# PART-03-_R150-199.net
KiCad netlist of a schematic drawn in Altium Designer
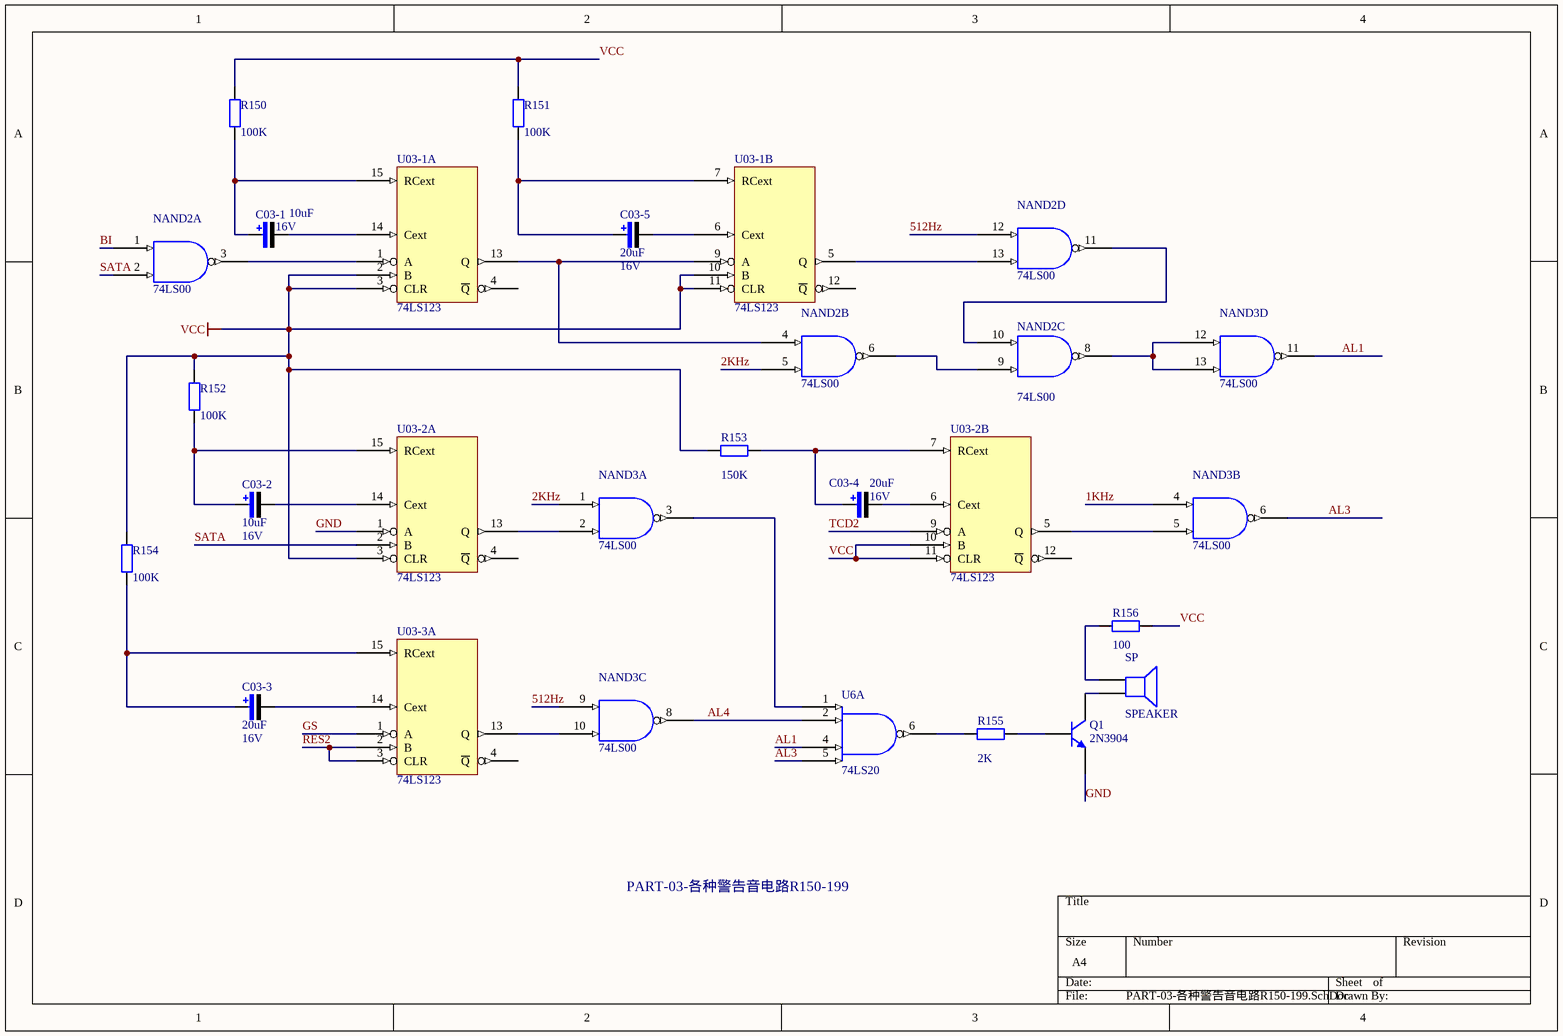
[diagram p0: PART-03-各种警告音电路R150-199.SchDoc]

(export (version "E")
  (design (tool "Eeschema 10.0.6"))
  (components
    (comp (ref "C03-1")
      (value "10uF")
      (footprint "C-RB-18")
      (description "极性电解电容")
      (fields
        (field (name "VOL") "16V")
        (field (name "Comment") "Cap Pol")
        (field (name "PUBLISHER") "Altium Limited")
      )
      (libsource (lib "Fszhang") (part "Cap Pol"))
    )
    (comp (ref "C03-2")
      (value "10uF")
      (footprint "C-RB-18")
      (description "极性电解电容")
      (fields
        (field (name "VOL") "16V")
        (field (name "Comment") "Cap Pol")
        (field (name "PUBLISHER") "Altium Limited")
      )
      (libsource (lib "Fszhang") (part "Cap Pol"))
    )
    (comp (ref "C03-3")
      (value "20uF")
      (footprint "C-RB-18")
      (description "极性电解电容")
      (fields
        (field (name "VOL") "16V")
        (field (name "Comment") "Cap Pol")
        (field (name "PUBLISHER") "Altium Limited")
      )
      (libsource (lib "Fszhang") (part "Cap Pol"))
    )
    (comp (ref "C03-4")
      (value "20uF")
      (footprint "C-RB-18")
      (description "极性电解电容")
      (fields
        (field (name "VOL") "16V")
        (field (name "Comment") "Cap Pol")
        (field (name "PUBLISHER") "Altium Limited")
      )
      (libsource (lib "Fszhang") (part "Cap Pol"))
    )
    (comp (ref "C03-5")
      (value "20uF")
      (footprint "C-RB-18")
      (description "极性电解电容")
      (fields
        (field (name "VOL") "16V")
        (field (name "Comment") "Cap Pol")
        (field (name "PUBLISHER") "Altium Limited")
      )
      (libsource (lib "Fszhang") (part "Cap Pol"))
    )
    (comp (ref "NAND2")
      (value "74LS00")
      (footprint "DIP-14")
      (libsource (lib "Protel DOS Schematic TTL") (part "74LS00"))
    )
    (comp (ref "NAND3")
      (value "74LS00")
      (footprint "DIP-14")
      (libsource (lib "Protel DOS Schematic TTL") (part "74LS00"))
    )
    (comp (ref "Q1")
      (value "2N3904")
      (footprint "TO-92A")
      (description "NPN General Purpose Amplifier")
      (fields (field (name "PUBLISHER") "Altium Limited"))
      (libsource (lib "Miscellaneous Devices") (part "2N3904"))
    )
    (comp (ref "R150")
      (value "100K")
      (footprint "AXIAL-0.4")
      (description "Resistor")
      (fields (field (name "Comment") "Res2") (field (name "PUBLISHER") "Altium Limited"))
      (libsource (lib "Miscellaneous Devices") (part "Res2"))
    )
    (comp (ref "R151")
      (value "100K")
      (footprint "AXIAL-0.4")
      (description "Resistor")
      (fields (field (name "Comment") "Res2") (field (name "PUBLISHER") "Altium Limited"))
      (libsource (lib "Miscellaneous Devices") (part "Res2"))
    )
    (comp (ref "R152")
      (value "100K")
      (footprint "AXIAL-0.4")
      (description "Resistor")
      (fields (field (name "Comment") "Res2") (field (name "PUBLISHER") "Altium Limited"))
      (libsource (lib "Miscellaneous Devices") (part "Res2"))
    )
    (comp (ref "R153")
      (value "150K")
      (footprint "AXIAL-0.4")
      (description "Resistor")
      (fields (field (name "Comment") "Res2") (field (name "PUBLISHER") "Altium Limited"))
      (libsource (lib "") (part "Res2_1"))
    )
    (comp (ref "R154")
      (value "100K")
      (footprint "AXIAL-0.4")
      (description "Resistor")
      (fields (field (name "Comment") "Res2") (field (name "PUBLISHER") "Altium Limited"))
      (libsource (lib "Miscellaneous Devices") (part "Res2"))
    )
    (comp (ref "R155")
      (value "2K")
      (footprint "AXIAL-0.4")
      (description "Resistor")
      (fields (field (name "Comment") "Res2") (field (name "PUBLISHER") "Altium Limited"))
      (libsource (lib "") (part "Res2_1"))
    )
    (comp (ref "R156")
      (value "100")
      (footprint "AXIAL-0.4")
      (description "Resistor")
      (fields (field (name "Comment") "Res2") (field (name "PUBLISHER") "Altium Limited"))
      (libsource (lib "") (part "Res2_1"))
    )
    (comp (ref "SP") (value "SPEAKER") (libsource (lib "Miscellaneous Devices") (part "SPEAKER")))
    (comp (ref "U03-1")
      (value "74LS123")
      (footprint "DIP-16")
      (libsource (lib "Protel DOS Schematic TTL") (part "74LS123"))
    )
    (comp (ref "U03-2")
      (value "74LS123")
      (footprint "DIP-16")
      (libsource (lib "Protel DOS Schematic TTL") (part "74LS123"))
    )
    (comp (ref "U03-3")
      (value "74LS123")
      (footprint "DIP-16")
      (libsource (lib "Protel DOS Schematic TTL") (part "74LS123"))
    )
    (comp (ref "U6") (value "74LS20") (footprint "DIP-14") (libsource (lib "Schematic TTL") (part "74LS20")))
  )
  (nets
    (net (code "1") (name "/1KHz") (class "Default") (node (ref "NAND3") (pin "4") (pintype "input")))
    (net (code "2") (name "/2KHz") (class "Default")
      (node (ref "NAND2") (pin "5") (pintype "input"))
      (node (ref "NAND3") (pin "1") (pintype "input"))
    )
    (net (code "3") (name "/512Hz") (class "Default")
      (node (ref "NAND2") (pin "12") (pintype "input"))
      (node (ref "NAND3") (pin "9") (pintype "input"))
    )
    (net (code "4") (name "/AL1") (class "Default")
      (node (ref "NAND3") (pin "11") (pintype "output"))
      (node (ref "U6") (pin "4") (pintype "input"))
    )
    (net (code "5") (name "/AL3") (class "Default")
      (node (ref "NAND3") (pin "6") (pintype "output"))
      (node (ref "U6") (pin "5") (pintype "input"))
    )
    (net (code "6") (name "/AL4") (class "Default")
      (node (ref "NAND3") (pin "8") (pintype "output"))
      (node (ref "U6") (pin "2") (pintype "input"))
    )
    (net (code "7") (name "/BI") (class "Default") (node (ref "NAND2") (pin "1") (pintype "input")))
    (net (code "8") (name "/GS") (class "Default")
      (node (ref "U03-3") (pin "1") (pinfunction "A_1") (pintype "input"))
    )
    (net (code "9") (name "/RES2") (class "Default")
      (node (ref "U03-3") (pin "2") (pinfunction "B_2") (pintype "input"))
      (node (ref "U03-3") (pin "3") (pinfunction "CLR_3") (pintype "input"))
    )
    (net (code "10") (name "/SATA") (class "Default")
      (node (ref "NAND2") (pin "2") (pintype "input"))
      (node (ref "U03-2") (pin "2") (pinfunction "B_2") (pintype "input"))
    )
    (net (code "11") (name "/TCD2") (class "Default")
      (node (ref "U03-2") (pin "9") (pinfunction "A_9") (pintype "input"))
    )
    (net (code "12") (name "GND") (class "Default")
      (node (ref "NAND2") (pin "7") (pinfunction "GND_7") (pintype "power_in"))
      (node (ref "NAND3") (pin "7") (pinfunction "GND_7") (pintype "power_in"))
      (node (ref "Q1") (pin "1") (pinfunction "E_1") (pintype "passive"))
      (node (ref "U03-1") (pin "8") (pinfunction "GND_8") (pintype "power_in"))
      (node (ref "U03-2") (pin "1") (pinfunction "A_1") (pintype "input"))
      (node (ref "U03-2") (pin "8") (pinfunction "GND_8") (pintype "power_in"))
      (node (ref "U03-3") (pin "8") (pinfunction "GND_8") (pintype "power_in"))
      (node (ref "U6") (pin "7") (pinfunction "GND_7") (pintype "power_in"))
    )
    (net (code "13") (name "Net-(NAND2-Pad6)") (class "Default")
      (node (ref "NAND2") (pin "6") (pintype "output"))
      (node (ref "NAND2") (pin "9") (pintype "input"))
    )
    (net (code "14") (name "Net-(NAND2-Pad8)") (class "Default")
      (node (ref "NAND2") (pin "8") (pintype "output"))
      (node (ref "NAND3") (pin "12") (pintype "input"))
      (node (ref "NAND3") (pin "13") (pintype "input"))
    )
    (net (code "15") (name "Net-(NAND2-Pad10)") (class "Default")
      (node (ref "NAND2") (pin "10") (pintype "input"))
      (node (ref "NAND2") (pin "11") (pintype "output"))
    )
    (net (code "16") (name "Net-(NAND3-Pad3)") (class "Default")
      (node (ref "NAND3") (pin "3") (pintype "output"))
      (node (ref "U6") (pin "1") (pintype "input"))
    )
    (net (code "17") (name "Net-(Q1-B)") (class "Default")
      (node (ref "Q1") (pin "2") (pinfunction "B_2") (pintype "passive"))
      (node (ref "R155") (pin "2") (pinfunction "2_2") (pintype "passive"))
    )
    (net (code "18") (name "Net-(Q1-C)") (class "Default")
      (node (ref "Q1") (pin "3") (pinfunction "C_3") (pintype "passive"))
      (node (ref "SP") (pin "2") (pinfunction "2_2") (pintype "passive"))
    )
    (net (code "19") (name "Net-(R155-Pad1)") (class "Default")
      (node (ref "R155") (pin "1") (pinfunction "1_1") (pintype "passive"))
      (node (ref "U6") (pin "6") (pintype "output"))
    )
    (net (code "20") (name "Net-(R156-Pad1)") (class "Default")
      (node (ref "R156") (pin "1") (pinfunction "1_1") (pintype "passive"))
      (node (ref "SP") (pin "1") (pinfunction "1_1") (pintype "passive"))
    )
    (net (code "21") (name "Net-(U03-1A-A)") (class "Default")
      (node (ref "NAND2") (pin "3") (pintype "output"))
      (node (ref "U03-1") (pin "1") (pinfunction "A_1") (pintype "input"))
    )
    (net (code "22") (name "Net-(U03-1A-Cext)") (class "Default")
      (node (ref "C03-1") (pin "2") (pinfunction "2_2") (pintype "passive"))
      (node (ref "U03-1") (pin "14") (pinfunction "Cext_14") (pintype "input"))
    )
    (net (code "23") (name "Net-(U03-1A-Q)") (class "Default")
      (node (ref "NAND2") (pin "4") (pintype "input"))
      (node (ref "U03-1") (pin "13") (pinfunction "Q_13") (pintype "output"))
      (node (ref "U03-1") (pin "9") (pinfunction "A_9") (pintype "input"))
    )
    (net (code "24") (name "Net-(U03-1A-RCext)") (class "Default")
      (node (ref "C03-1") (pin "1") (pinfunction "1_1") (pintype "passive"))
      (node (ref "R150") (pin "1") (pinfunction "1_1") (pintype "passive"))
      (node (ref "U03-1") (pin "15") (pinfunction "RCext_15") (pintype "input"))
    )
    (net (code "25") (name "Net-(U03-1B-Cext)") (class "Default")
      (node (ref "C03-5") (pin "2") (pinfunction "2_2") (pintype "passive"))
      (node (ref "U03-1") (pin "6") (pinfunction "Cext_6") (pintype "input"))
    )
    (net (code "26") (name "Net-(U03-1B-Q)") (class "Default")
      (node (ref "NAND2") (pin "13") (pintype "input"))
      (node (ref "U03-1") (pin "5") (pinfunction "Q_5") (pintype "output"))
    )
    (net (code "27") (name "Net-(U03-1B-RCext)") (class "Default")
      (node (ref "C03-5") (pin "1") (pinfunction "1_1") (pintype "passive"))
      (node (ref "R151") (pin "1") (pinfunction "1_1") (pintype "passive"))
      (node (ref "U03-1") (pin "7") (pinfunction "RCext_7") (pintype "input"))
    )
    (net (code "28") (name "Net-(U03-2A-Cext)") (class "Default")
      (node (ref "C03-2") (pin "2") (pinfunction "2_2") (pintype "passive"))
      (node (ref "U03-2") (pin "14") (pinfunction "Cext_14") (pintype "input"))
    )
    (net (code "29") (name "Net-(U03-2A-Q)") (class "Default")
      (node (ref "NAND3") (pin "2") (pintype "input"))
      (node (ref "U03-2") (pin "13") (pinfunction "Q_13") (pintype "output"))
    )
    (net (code "30") (name "Net-(U03-2A-RCext)") (class "Default")
      (node (ref "C03-2") (pin "1") (pinfunction "1_1") (pintype "passive"))
      (node (ref "R152") (pin "1") (pinfunction "1_1") (pintype "passive"))
      (node (ref "U03-2") (pin "15") (pinfunction "RCext_15") (pintype "input"))
    )
    (net (code "31") (name "Net-(U03-2B-Cext)") (class "Default")
      (node (ref "C03-4") (pin "2") (pinfunction "2_2") (pintype "passive"))
      (node (ref "U03-2") (pin "6") (pinfunction "Cext_6") (pintype "input"))
    )
    (net (code "32") (name "Net-(U03-2B-Q)") (class "Default")
      (node (ref "NAND3") (pin "5") (pintype "input"))
      (node (ref "U03-2") (pin "5") (pinfunction "Q_5") (pintype "output"))
    )
    (net (code "33") (name "Net-(U03-2B-RCext)") (class "Default")
      (node (ref "C03-4") (pin "1") (pinfunction "1_1") (pintype "passive"))
      (node (ref "R153") (pin "2") (pinfunction "2_2") (pintype "passive"))
      (node (ref "U03-2") (pin "7") (pinfunction "RCext_7") (pintype "input"))
    )
    (net (code "34") (name "Net-(U03-3A-Cext)") (class "Default")
      (node (ref "C03-3") (pin "2") (pinfunction "2_2") (pintype "passive"))
      (node (ref "U03-3") (pin "14") (pinfunction "Cext_14") (pintype "input"))
    )
    (net (code "35") (name "Net-(U03-3A-Q)") (class "Default")
      (node (ref "NAND3") (pin "10") (pintype "input"))
      (node (ref "U03-3") (pin "13") (pinfunction "Q_13") (pintype "output"))
    )
    (net (code "36") (name "Net-(U03-3A-RCext)") (class "Default")
      (node (ref "C03-3") (pin "1") (pinfunction "1_1") (pintype "passive"))
      (node (ref "R154") (pin "1") (pinfunction "1_1") (pintype "passive"))
      (node (ref "U03-3") (pin "15") (pinfunction "RCext_15") (pintype "input"))
    )
    (net (code "37") (name "VCC") (class "Default")
      (node (ref "NAND2") (pin "14") (pinfunction "VCC_14") (pintype "power_in"))
      (node (ref "NAND3") (pin "14") (pinfunction "VCC_14") (pintype "power_in"))
      (node (ref "R150") (pin "2") (pinfunction "2_2") (pintype "passive"))
      (node (ref "R151") (pin "2") (pinfunction "2_2") (pintype "passive"))
      (node (ref "R152") (pin "2") (pinfunction "2_2") (pintype "passive"))
      (node (ref "R153") (pin "1") (pinfunction "1_1") (pintype "passive"))
      (node (ref "R154") (pin "2") (pinfunction "2_2") (pintype "passive"))
      (node (ref "R156") (pin "2") (pinfunction "2_2") (pintype "passive"))
      (node (ref "U03-1") (pin "10") (pinfunction "B_10") (pintype "input"))
      (node (ref "U03-1") (pin "11") (pinfunction "CLR_11") (pintype "input"))
      (node (ref "U03-1") (pin "16") (pinfunction "VCC_16") (pintype "power_in"))
      (node (ref "U03-1") (pin "2") (pinfunction "B_2") (pintype "input"))
      (node (ref "U03-1") (pin "3") (pinfunction "CLR_3") (pintype "input"))
      (node (ref "U03-2") (pin "10") (pinfunction "B_10") (pintype "input"))
      (node (ref "U03-2") (pin "11") (pinfunction "CLR_11") (pintype "input"))
      (node (ref "U03-2") (pin "16") (pinfunction "VCC_16") (pintype "power_in"))
      (node (ref "U03-2") (pin "3") (pinfunction "CLR_3") (pintype "input"))
      (node (ref "U03-3") (pin "16") (pinfunction "VCC_16") (pintype "power_in"))
      (node (ref "U6") (pin "14") (pinfunction "VCC_14") (pintype "power_in"))
    )
    (net (code "38") (name "unconnected-(U03-1A-~{Q}-Pad4)") (class "Default")
      (node (ref "U03-1") (pin "4") (pinfunction "~{Q}_4") (pintype "output"))
    )
    (net (code "39") (name "unconnected-(U03-1B-~{Q}-Pad12)") (class "Default")
      (node (ref "U03-1") (pin "12") (pinfunction "~{Q}_12") (pintype "output"))
    )
    (net (code "40") (name "unconnected-(U03-2A-~{Q}-Pad4)") (class "Default")
      (node (ref "U03-2") (pin "4") (pinfunction "~{Q}_4") (pintype "output"))
    )
    (net (code "41") (name "unconnected-(U03-2B-~{Q}-Pad12)") (class "Default")
      (node (ref "U03-2") (pin "12") (pinfunction "~{Q}_12") (pintype "output"))
    )
    (net (code "42") (name "unconnected-(U03-3A-~{Q}-Pad4)") (class "Default")
      (node (ref "U03-3") (pin "4") (pinfunction "~{Q}_4") (pintype "output"))
    )
  )
)
